# uARM.net
KiCad netlist of a schematic drawn in Altium Designer
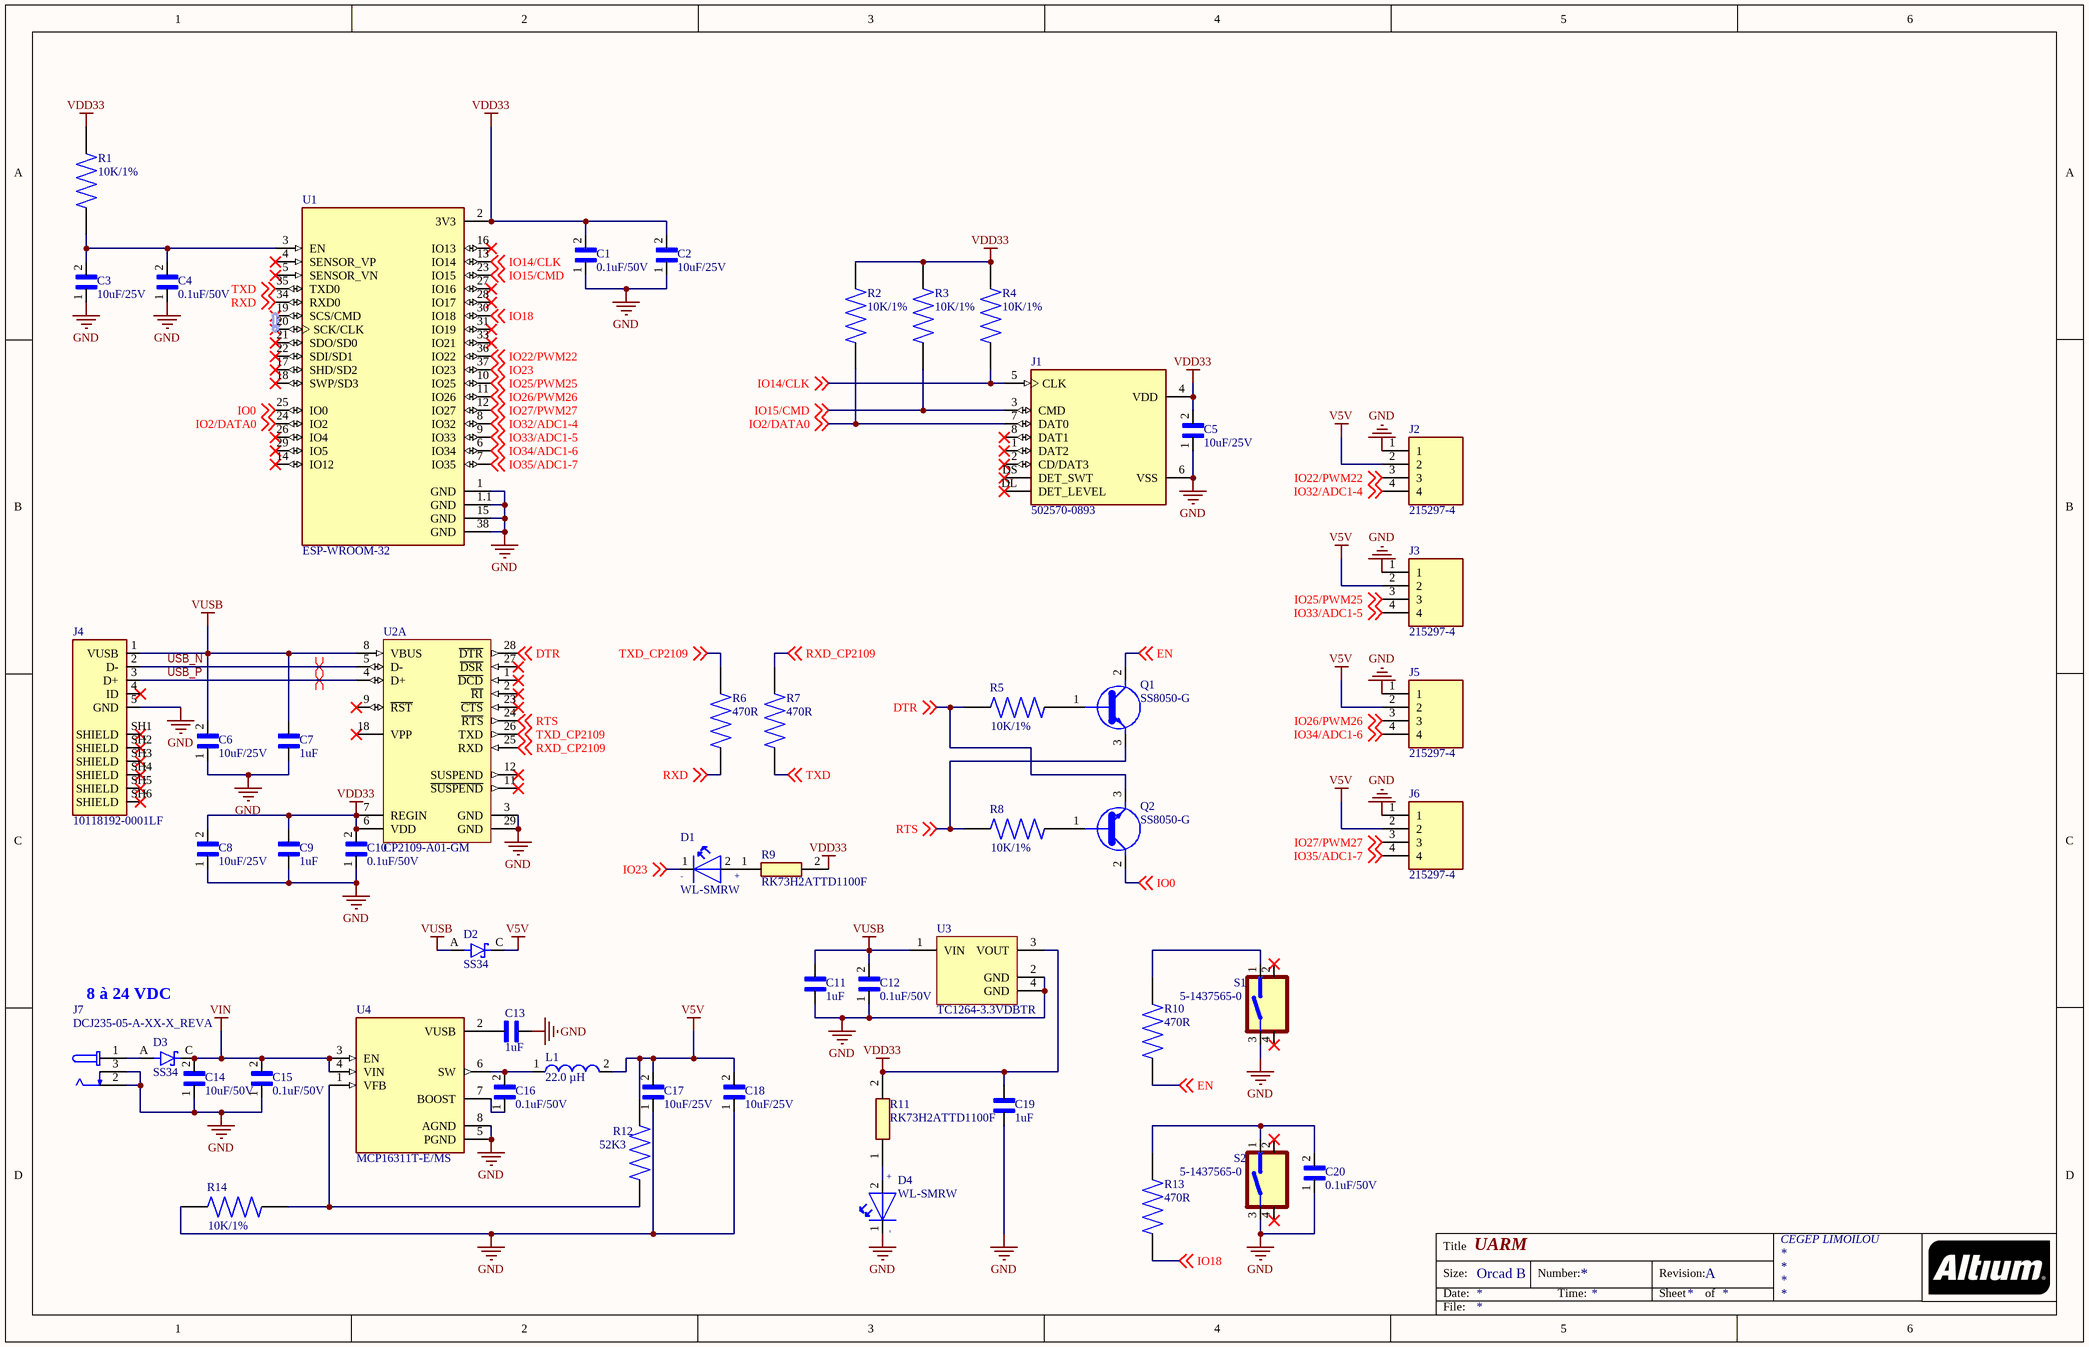
[diagram p0: uARM.SchDoc]

(export (version "E")
  (design (tool "Eeschema 10.0.6"))
  (components
    (comp (ref "C1")
      (value "0.1uF/50V")
      (footprint "RESC2012X60N")
      (description ".1UF 50V 10% 0805")
      (fields (field (name "MF") "{'manufacturer': u'AVX'}") (field (name "MP") "08055C104KAT4A"))
      (libsource (lib "*") (part "08055C104KAT4A"))
    )
    (comp (ref "C2")
      (value "10uF/25V")
      (footprint "RESC2012X60N")
      (description "Cap Ceramic 10uF 25V X5R 10% SMD 0805 85Â°C Embossed T/R")
      (fields (field (name "MP") "CL21A106KAYNNNE") (field (name "MF") "{'manufacturer': u'Samsung'}"))
      (libsource (lib "*") (part "CL21A106KAYNNNE"))
    )
    (comp (ref "C3")
      (value "10uF/25V")
      (footprint "RESC2012X60N")
      (description "Cap Ceramic 10uF 25V X5R 10% SMD 0805 85Â°C Embossed T/R")
      (fields (field (name "MP") "CL21A106KAYNNNE") (field (name "MF") "{'manufacturer': u'Samsung'}"))
      (libsource (lib "*") (part "CL21A106KAYNNNE"))
    )
    (comp (ref "C4")
      (value "0.1uF/50V")
      (footprint "RESC2012X60N")
      (description ".1UF 50V 10% 0805")
      (fields (field (name "MF") "{'manufacturer': u'AVX'}") (field (name "MP") "08055C104KAT4A"))
      (libsource (lib "*") (part "08055C104KAT4A"))
    )
    (comp (ref "C5")
      (value "10uF/25V")
      (footprint "CL21A106KAYNNNE:CAPC2012X135N")
      (description "Cap Ceramic 10uF 25V X5R 10% SMD 0805 85Â°C Embossed T/R")
      (fields (field (name "MP") "CL21A106KAYNNNE") (field (name "MF") "{'manufacturer': u'Samsung'}"))
      (libsource (lib "*") (part "CL21A106KAYNNNE"))
    )
    (comp (ref "C6")
      (value "10uF/25V")
      (footprint "CL21A106KAYNNNE:CAPC2012X135N")
      (description "Cap Ceramic 10uF 25V X5R 10% SMD 0805 85Â°C Embossed T/R")
      (fields (field (name "MP") "CL21A106KAYNNNE") (field (name "MF") "{'manufacturer': u'Samsung'}"))
      (libsource (lib "*") (part "CL21A106KAYNNNE"))
    )
    (comp (ref "C7")
      (value "1uF")
      (footprint "885012207022:WCAP-CSGP_885012207022")
      (fields
        (field (name "MF") "{'manufacturer': u'Wurth Electronics Inc'}")
        (field (name "MP") "885012207022")
      )
      (libsource (lib "*") (part "885012207022"))
    )
    (comp (ref "C8")
      (value "10uF/25V")
      (footprint "CL21A106KAYNNNE:CAPC2012X135N")
      (description "Cap Ceramic 10uF 25V X5R 10% SMD 0805 85Â°C Embossed T/R")
      (fields (field (name "MP") "CL21A106KAYNNNE") (field (name "MF") "{'manufacturer': u'Samsung'}"))
      (libsource (lib "*") (part "CL21A106KAYNNNE"))
    )
    (comp (ref "C9")
      (value "1uF")
      (footprint "885012207022:WCAP-CSGP_885012207022")
      (fields
        (field (name "MF") "{'manufacturer': u'Wurth Electronics Inc'}")
        (field (name "MP") "885012207022")
      )
      (libsource (lib "*") (part "885012207022"))
    )
    (comp (ref "C10")
      (value "0.1uF/50V")
      (footprint "08055C104KAT4A:CAPC2012X94N")
      (description ".1UF 50V 10% 0805")
      (fields (field (name "MF") "{'manufacturer': u'AVX'}") (field (name "MP") "08055C104KAT4A"))
      (libsource (lib "*") (part "08055C104KAT4A"))
    )
    (comp (ref "C11")
      (value "1uF")
      (footprint "885012207022:WCAP-CSGP_885012207022")
      (fields
        (field (name "MF") "{'manufacturer': u'Wurth Electronics Inc'}")
        (field (name "MP") "885012207022")
      )
      (libsource (lib "*") (part "885012207022"))
    )
    (comp (ref "C12")
      (value "0.1uF/50V")
      (footprint "08055C104KAT4A:CAPC2012X94N")
      (description ".1UF 50V 10% 0805")
      (fields (field (name "MF") "{'manufacturer': u'AVX'}") (field (name "MP") "08055C104KAT4A"))
      (libsource (lib "*") (part "08055C104KAT4A"))
    )
    (comp (ref "C13")
      (value "1uF")
      (footprint "885012207022:WCAP-CSGP_885012207022")
      (fields
        (field (name "MF") "{'manufacturer': u'Wurth Electronics Inc'}")
        (field (name "MP") "885012207022")
      )
      (libsource (lib "") (part "885012207022_1"))
    )
    (comp (ref "C14")
      (value "10uF/50V")
      (footprint "GRM21BR61H106KE43L:CAPC2012X145N")
      (description "SMD Capacitor X5R(EIA) with Capacitance: 10uF Tol. 10%. Rated Voltage: 50Vdc")
      (fields
        (field (name "MP") "GRM21BR61H106KE43L")
        (field (name "MF") "{'manufacturer': u'Murata Electronics'}")
      )
      (libsource (lib "*") (part "GRM21BR61H106KE43L"))
    )
    (comp (ref "C15")
      (value "0.1uF/50V")
      (footprint "08055C104KAT4A:CAPC2012X94N")
      (description ".1UF 50V 10% 0805")
      (fields (field (name "MF") "{'manufacturer': u'AVX'}") (field (name "MP") "08055C104KAT4A"))
      (libsource (lib "*") (part "08055C104KAT4A"))
    )
    (comp (ref "C16")
      (value "0.1uF/50V")
      (footprint "08055C104KAT4A:CAPC2012X94N")
      (description ".1UF 50V 10% 0805")
      (fields (field (name "MF") "{'manufacturer': u'AVX'}") (field (name "MP") "08055C104KAT4A"))
      (libsource (lib "*") (part "08055C104KAT4A"))
    )
    (comp (ref "C17")
      (value "10uF/25V")
      (footprint "CL21A106KAYNNNE:CAPC2012X135N")
      (description "Cap Ceramic 10uF 25V X5R 10% SMD 0805 85Â°C Embossed T/R")
      (fields (field (name "MP") "CL21A106KAYNNNE") (field (name "MF") "{'manufacturer': u'Samsung'}"))
      (libsource (lib "*") (part "CL21A106KAYNNNE"))
    )
    (comp (ref "C18")
      (value "10uF/25V")
      (footprint "CL21A106KAYNNNE:CAPC2012X135N")
      (description "Cap Ceramic 10uF 25V X5R 10% SMD 0805 85Â°C Embossed T/R")
      (fields (field (name "MP") "CL21A106KAYNNNE") (field (name "MF") "{'manufacturer': u'Samsung'}"))
      (libsource (lib "*") (part "CL21A106KAYNNNE"))
    )
    (comp (ref "C19")
      (value "1uF")
      (footprint "885012207022:WCAP-CSGP_885012207022")
      (fields
        (field (name "MF") "{'manufacturer': u'Wurth Electronics Inc'}")
        (field (name "MP") "885012207022")
      )
      (libsource (lib "*") (part "885012207022"))
    )
    (comp (ref "C20")
      (value "0.1uF/50V")
      (footprint "08055C104KAT4A:CAPC2012X94N")
      (description ".1UF 50V 10% 0805")
      (fields (field (name "MF") "{'manufacturer': u'AVX'}") (field (name "MP") "08055C104KAT4A"))
      (libsource (lib "*") (part "08055C104KAT4A"))
    )
    (comp (ref "D1")
      (value "WL-SMRW")
      (footprint "156120GS75000:WL-SMRW-1206-RECT")
      (fields (field (name "MF") "{'manufacturer': u'Wurth Electronics'}"))
      (libsource (lib "*") (part "WL-SMRW"))
    )
    (comp (ref "D2")
      (value "SS34")
      (footprint "SS34:DIOM7959X265N")
      (description "Diode Schottky 40V 3A 2-Pin SMC T/R")
      (fields (field (name "MF") "{'manufacturer': u'ON Semiconductor'}"))
      (libsource (lib "*") (part "SS34"))
    )
    (comp (ref "D3")
      (value "SS34")
      (footprint "SS34:DIOM7959X265N")
      (description "Diode Schottky 40V 3A 2-Pin SMC T/R")
      (fields (field (name "MF") "{'manufacturer': u'ON Semiconductor'}"))
      (libsource (lib "*") (part "SS34"))
    )
    (comp (ref "D4")
      (value "WL-SMRW")
      (footprint "156120GS75000:WL-SMRW-1206-RECT")
      (fields (field (name "MF") "{'manufacturer': u'Wurth Electronics'}"))
      (libsource (lib "*") (part "WL-SMRW"))
    )
    (comp (ref "J1")
      (value "502570-0893")
      (footprint "502570-0893:MOLEX_502570-0893")
      (fields (field (name "MF") "{'manufacturer': u'Molex'}"))
      (libsource (lib "*") (part "502570-0893"))
    )
    (comp (ref "J2")
      (value "215297-4")
      (footprint "215297-4:TE_215297-4")
      (fields (field (name "MF") "{'manufacturer': u'TE Connectivity'}"))
      (libsource (lib "*") (part "215297-4"))
    )
    (comp (ref "J3")
      (value "215297-4")
      (footprint "215297-4:TE_215297-4")
      (fields (field (name "MF") "{'manufacturer': u'TE Connectivity'}"))
      (libsource (lib "*") (part "215297-4"))
    )
    (comp (ref "J4")
      (value "10118192-0001LF")
      (footprint "10118192-0001LF:AMPHENOL_10118192-0001LF")
      (description "Single Port 5 Contact Horizontal Right Angle Shielded Micro B USB 2.0 Connector")
      (fields (field (name "MF") "{'manufacturer': u'FCI'}"))
      (libsource (lib "*") (part "10118192-0001LF"))
    )
    (comp (ref "J5")
      (value "215297-4")
      (footprint "215297-4:TE_215297-4")
      (fields (field (name "MF") "{'manufacturer': u'TE Connectivity'}"))
      (libsource (lib "*") (part "215297-4"))
    )
    (comp (ref "J6")
      (value "215297-4")
      (footprint "215297-4:TE_215297-4")
      (fields (field (name "MF") "{'manufacturer': u'TE Connectivity'}"))
      (libsource (lib "*") (part "215297-4"))
    )
    (comp (ref "J7")
      (value "DCJ235-05-A-XX-X_REVA")
      (footprint "DCJ235-05-A-K1-A:GCT_DCJ235-05-A-XX-X_REVA")
      (description "DC Power Jack, Thru-Hole, Horizontal, with Locating Pegs, D2.35mm")
      (fields (field (name "MF") "{'manufacturer': u'Global Connector Technology'}"))
      (libsource (lib "*") (part "DCJ235-05-A-XX-X_REVA"))
    )
    (comp (ref "L1")
      (value "744773122")
      (footprint "WE-PD2-S")
      (description "SMD Power Inductor WE-PD2, L = 22.0 µH")
      (fields (field (name "INDUCTANCE") "22.0 µH"))
      (libsource (lib "Wurth_Electronics_744773122") (part "744773122"))
    )
    (comp (ref "Q1")
      (value "SS8050-G")
      (footprint "SS8050-G:MBTB-T-SOT23")
      (fields (field (name "MF") "{'manufacturer': u'Comchip Technology'}"))
      (libsource (lib "*") (part "SS8050-G"))
    )
    (comp (ref "Q2")
      (value "SS8050-G")
      (footprint "SS8050-G:MBTB-T-SOT23")
      (fields (field (name "MF") "{'manufacturer': u'Comchip Technology'}"))
      (libsource (lib "*") (part "SS8050-G"))
    )
    (comp (ref "R1")
      (value "10K/1%")
      (footprint "ESR10EZPF1002:RESC2012X65N")
      (description "RES SMD 10K OHM 1% 0.4W 0805")
      (fields (field (name "MF") "{'manufacturer': u'Rohm'}") (field (name "MP") "ESR10EZPF1002"))
      (libsource (lib "*") (part "ESR10EZPF1002"))
    )
    (comp (ref "R2")
      (value "10K/1%")
      (footprint "ESR10EZPF1002:RESC2012X65N")
      (description "RES SMD 10K OHM 1% 0.4W 0805")
      (fields (field (name "MF") "{'manufacturer': u'Rohm'}") (field (name "MP") "ESR10EZPF1002"))
      (libsource (lib "*") (part "ESR10EZPF1002"))
    )
    (comp (ref "R3")
      (value "10K/1%")
      (footprint "ESR10EZPF1002:RESC2012X65N")
      (description "RES SMD 10K OHM 1% 0.4W 0805")
      (fields (field (name "MF") "{'manufacturer': u'Rohm'}") (field (name "MP") "ESR10EZPF1002"))
      (libsource (lib "*") (part "ESR10EZPF1002"))
    )
    (comp (ref "R4")
      (value "10K/1%")
      (footprint "ESR10EZPF1002:RESC2012X65N")
      (description "RES SMD 10K OHM 1% 0.4W 0805")
      (fields (field (name "MF") "{'manufacturer': u'Rohm'}") (field (name "MP") "ESR10EZPF1002"))
      (libsource (lib "*") (part "ESR10EZPF1002"))
    )
    (comp (ref "R5")
      (value "10K/1%")
      (footprint "ESR10EZPF1002:RESC2012X65N")
      (description "RES SMD 10K OHM 1% 0.4W 0805")
      (fields (field (name "MF") "{'manufacturer': u'Rohm'}") (field (name "MP") "ESR10EZPF1002"))
      (libsource (lib "*") (part "ESR10EZPF1002"))
    )
    (comp (ref "R6")
      (value "470R")
      (footprint "ERJ-PB6B4700V:RESC2012X70N")
      (fields (field (name "MP") "ERJ-PB6B4700V") (field (name "MF") "{'manufacturer': u'Panasonic'}"))
      (libsource (lib "*") (part "ERJ-PB6B4700V"))
    )
    (comp (ref "R7")
      (value "470R")
      (footprint "ERJ-PB6B4700V:RESC2012X70N")
      (fields (field (name "MP") "ERJ-PB6B4700V") (field (name "MF") "{'manufacturer': u'Panasonic'}"))
      (libsource (lib "*") (part "ERJ-PB6B4700V"))
    )
    (comp (ref "R8")
      (value "10K/1%")
      (footprint "ESR10EZPF1002:RESC2012X65N")
      (description "RES SMD 10K OHM 1% 0.4W 0805")
      (fields (field (name "MF") "{'manufacturer': u'Rohm'}") (field (name "MP") "ESR10EZPF1002"))
      (libsource (lib "*") (part "ESR10EZPF1002"))
    )
    (comp (ref "R9")
      (value "RK73H2ATTD1100F")
      (footprint "SamacSys:RESC2012X60N")
      (description "Resistor")
      (libsource (lib "*") (part "RK73H2ATTD1100F"))
    )
    (comp (ref "R10")
      (value "470R")
      (footprint "ERJ-PB6B4700V:RESC2012X70N")
      (fields (field (name "MP") "ERJ-PB6B4700V") (field (name "MF") "{'manufacturer': u'Panasonic'}"))
      (libsource (lib "*") (part "ERJ-PB6B4700V"))
    )
    (comp (ref "R11")
      (value "RK73H2ATTD1100F")
      (footprint "SamacSys:RESC2012X60N")
      (description "Resistor")
      (libsource (lib "") (part "RK73H2ATTD1100F_1"))
    )
    (comp (ref "R12")
      (value "52K3")
      (footprint "RESC2012X60N")
      (fields (field (name "MP") "ERJ-PB6B5232V"))
      (libsource (lib "ERJ-PB6B5232V") (part "ERJ-PB6B5232V"))
    )
    (comp (ref "R13")
      (value "470R")
      (footprint "ERJ-PB6B4700V:RESC2012X70N")
      (fields (field (name "MP") "ERJ-PB6B4700V") (field (name "MF") "{'manufacturer': u'Panasonic'}"))
      (libsource (lib "*") (part "ERJ-PB6B4700V"))
    )
    (comp (ref "R14")
      (value "10K/1%")
      (footprint "ESR10EZPF1002:RESC2012X65N")
      (description "RES SMD 10K OHM 1% 0.4W 0805")
      (fields (field (name "MF") "{'manufacturer': u'Rohm'}") (field (name "MP") "ESR10EZPF1002"))
      (libsource (lib "*") (part "ESR10EZPF1002"))
    )
    (comp (ref "S1")
      (value "5-1437565-0")
      (footprint "FSM6JSMATR:SW_5-1437565-0")
      (description "Switch Tactile OFF (ON) Round Button Gull Wing 0.05A 12VDC 1.57N SMD T/R")
      (fields (field (name "MF") "{'manufacturer': u'TE Connectivity'}"))
      (libsource (lib "*") (part "5-1437565-0"))
    )
    (comp (ref "S2")
      (value "5-1437565-0")
      (footprint "FSM6JSMATR:SW_5-1437565-0")
      (description "Switch Tactile OFF (ON) Round Button Gull Wing 0.05A 12VDC 1.57N SMD T/R")
      (fields (field (name "MF") "{'manufacturer': u'TE Connectivity'}"))
      (libsource (lib "*") (part "5-1437565-0"))
    )
    (comp (ref "U1")
      (value "ESP-WROOM-32")
      (footprint "ESP-WROOM-32:MODULE_ESP-WROOM-32")
      (description "Module: combo; GPIO, I2C x2, I2S x2, SDIO, SPI x3, UART x3; 19.5dBm")
      (fields (field (name "MF") "{'manufacturer': u'Espressif Systems'}"))
      (libsource (lib "*") (part "ESP-WROOM-32"))
    )
    (comp (ref "U2")
      (value "CP2109-A01-GM")
      (footprint "SLAB-QFN-28-3125x3125TP_L")
      (description "Single-Chip USB to UART Bridge, 1024 Bytes EEPROM, -40 to 85 degC, 28-pin QFN, Tube")
      (fields (field (name "MANUFACTURER") "Silicon Labs"))
      (libsource (lib "Silicon_Labs_CP2109_A01_GM") (part "CP2109-A01-GM"))
    )
    (comp (ref "U3")
      (value "TC1264-3.3VDBTR")
      (footprint "SOT-223-DB3_L")
      (description "800 mA Fixed-Output CMOS LDO with Shutdown, 3-Pin SOT-223, Extended Temperature, Tape and Reel")
      (libsource (lib "Microchip_TC1264_3_3VDBTR") (part "TC1264-3.3VDBTR"))
    )
    (comp (ref "U4")
      (value "MCP16311T-E/MS")
      (footprint "MCP16311T-E_MS:SOP65P490X110-8N")
      (fields (field (name "MF") "{'manufacturer': u'Microchip Technology'}"))
      (libsource (lib "*") (part "MCP16311T-E/MS"))
    )
  )
  (nets
    (net (code "1") (name "/USB_N") (class "Default")
      (node (ref "J4") (pin "2") (pinfunction "D-_2") (pintype "passive"))
      (node (ref "U2") (pin "5") (pinfunction "D-_5") (pintype "bidirectional"))
    )
    (net (code "2") (name "/USB_P") (class "Default")
      (node (ref "J4") (pin "3") (pinfunction "D+_3") (pintype "passive"))
      (node (ref "U2") (pin "4") (pinfunction "D+_4") (pintype "bidirectional"))
    )
    (net (code "3") (name "DTR") (class "Default")
      (node (ref "Q2") (pin "3") (pinfunction "C_3") (pintype "bidirectional"))
      (node (ref "R5") (pin "1") (pinfunction "1_1") (pintype "passive"))
      (node (ref "U2") (pin "28") (pinfunction "~{DTR}_28") (pintype "output"))
    )
    (net (code "4") (name "EN") (class "Default")
      (node (ref "Q1") (pin "2") (pinfunction "E_2") (pintype "bidirectional"))
      (node (ref "R10") (pin "1") (pinfunction "1_1") (pintype "passive"))
    )
    (net (code "5") (name "GND") (class "Default")
      (node (ref "C1") (pin "1") (pinfunction "1_1") (pintype "passive"))
      (node (ref "C10") (pin "1") (pinfunction "1_1") (pintype "passive"))
      (node (ref "C11") (pin "2") (pinfunction "2_2") (pintype "passive"))
      (node (ref "C12") (pin "1") (pinfunction "1_1") (pintype "passive"))
      (node (ref "C13") (pin "1") (pinfunction "1_1") (pintype "passive"))
      (node (ref "C14") (pin "1") (pinfunction "1_1") (pintype "passive"))
      (node (ref "C15") (pin "1") (pinfunction "1_1") (pintype "passive"))
      (node (ref "C17") (pin "1") (pinfunction "1_1") (pintype "passive"))
      (node (ref "C18") (pin "1") (pinfunction "1_1") (pintype "passive"))
      (node (ref "C19") (pin "2") (pinfunction "2_2") (pintype "passive"))
      (node (ref "C2") (pin "1") (pinfunction "1_1") (pintype "passive"))
      (node (ref "C20") (pin "1") (pinfunction "1_1") (pintype "passive"))
      (node (ref "C3") (pin "1") (pinfunction "1_1") (pintype "passive"))
      (node (ref "C4") (pin "1") (pinfunction "1_1") (pintype "passive"))
      (node (ref "C5") (pin "1") (pinfunction "1_1") (pintype "passive"))
      (node (ref "C6") (pin "1") (pinfunction "1_1") (pintype "passive"))
      (node (ref "C7") (pin "2") (pinfunction "2_2") (pintype "passive"))
      (node (ref "C8") (pin "1") (pinfunction "1_1") (pintype "passive"))
      (node (ref "C9") (pin "2") (pinfunction "2_2") (pintype "passive"))
      (node (ref "D4") (pin "1") (pinfunction "NEG_1") (pintype "bidirectional"))
      (node (ref "J1") (pin "6") (pinfunction "VSS_6") (pintype "power_in"))
      (node (ref "J2") (pin "1") (pinfunction "1_1") (pintype "passive"))
      (node (ref "J3") (pin "1") (pinfunction "1_1") (pintype "passive"))
      (node (ref "J4") (pin "5") (pinfunction "GND_5") (pintype "passive"))
      (node (ref "J5") (pin "1") (pinfunction "1_1") (pintype "passive"))
      (node (ref "J6") (pin "1") (pinfunction "1_1") (pintype "passive"))
      (node (ref "J7") (pin "2") (pinfunction "2_2") (pintype "passive"))
      (node (ref "J7") (pin "3") (pinfunction "3_3") (pintype "passive"))
      (node (ref "R14") (pin "1") (pinfunction "1_1") (pintype "passive"))
      (node (ref "S1") (pin "3") (pinfunction "1_3") (pintype "passive"))
      (node (ref "S2") (pin "3") (pinfunction "1_3") (pintype "passive"))
      (node (ref "U1") (pin "1") (pinfunction "GND_1") (pintype "power_in"))
      (node (ref "U1") (pin "1.1") (pinfunction "GND_1.1") (pintype "power_in"))
      (node (ref "U1") (pin "15") (pinfunction "GND_15") (pintype "power_in"))
      (node (ref "U1") (pin "38") (pinfunction "GND_38") (pintype "power_in"))
      (node (ref "U2") (pin "29") (pinfunction "GND_29") (pintype "power_in"))
      (node (ref "U2") (pin "3") (pinfunction "GND_3") (pintype "power_in"))
      (node (ref "U3") (pin "2") (pinfunction "GND_2") (pintype "power_in"))
      (node (ref "U3") (pin "4") (pinfunction "GND_4") (pintype "power_in"))
      (node (ref "U4") (pin "5") (pinfunction "PGND_5") (pintype "power_in"))
      (node (ref "U4") (pin "8") (pinfunction "AGND_8") (pintype "power_in"))
    )
    (net (code "6") (name "IO0") (class "Default")
      (node (ref "Q2") (pin "2") (pinfunction "E_2") (pintype "bidirectional"))
      (node (ref "U1") (pin "25") (pinfunction "IO0_25") (pintype "bidirectional"))
    )
    (net (code "7") (name "IO2{slash}DATA0") (class "Default")
      (node (ref "J1") (pin "7") (pinfunction "DAT0_7") (pintype "bidirectional"))
      (node (ref "R2") (pin "1") (pinfunction "1_1") (pintype "passive"))
      (node (ref "U1") (pin "24") (pinfunction "IO2_24") (pintype "bidirectional"))
    )
    (net (code "8") (name "IO14{slash}CLK") (class "Default")
      (node (ref "J1") (pin "5") (pinfunction "CLK_5") (pintype "input"))
      (node (ref "R4") (pin "1") (pinfunction "1_1") (pintype "passive"))
      (node (ref "U1") (pin "13") (pinfunction "IO14_13") (pintype "bidirectional"))
    )
    (net (code "9") (name "IO15{slash}CMD") (class "Default")
      (node (ref "J1") (pin "3") (pinfunction "CMD_3") (pintype "bidirectional"))
      (node (ref "R3") (pin "1") (pinfunction "1_1") (pintype "passive"))
      (node (ref "U1") (pin "23") (pinfunction "IO15_23") (pintype "bidirectional"))
    )
    (net (code "10") (name "IO18") (class "Default")
      (node (ref "R13") (pin "1") (pinfunction "1_1") (pintype "passive"))
      (node (ref "U1") (pin "30") (pinfunction "IO18_30") (pintype "bidirectional"))
    )
    (net (code "11") (name "IO22{slash}PWM22") (class "Default")
      (node (ref "J2") (pin "3") (pinfunction "3_3") (pintype "passive"))
      (node (ref "U1") (pin "36") (pinfunction "IO22_36") (pintype "bidirectional"))
    )
    (net (code "12") (name "IO23") (class "Default")
      (node (ref "D1") (pin "1") (pinfunction "NEG_1") (pintype "bidirectional"))
      (node (ref "U1") (pin "37") (pinfunction "IO23_37") (pintype "bidirectional"))
    )
    (net (code "13") (name "IO25{slash}PWM25") (class "Default")
      (node (ref "J3") (pin "3") (pinfunction "3_3") (pintype "passive"))
      (node (ref "U1") (pin "10") (pinfunction "IO25_10") (pintype "bidirectional"))
    )
    (net (code "14") (name "IO26{slash}PWM26") (class "Default")
      (node (ref "J5") (pin "3") (pinfunction "3_3") (pintype "passive"))
      (node (ref "U1") (pin "11") (pinfunction "IO26_11") (pintype "bidirectional"))
    )
    (net (code "15") (name "IO27{slash}PWM27") (class "Default")
      (node (ref "J6") (pin "3") (pinfunction "3_3") (pintype "passive"))
      (node (ref "U1") (pin "12") (pinfunction "IO27_12") (pintype "bidirectional"))
    )
    (net (code "16") (name "IO32{slash}ADC1-4") (class "Default")
      (node (ref "J2") (pin "4") (pinfunction "4_4") (pintype "passive"))
      (node (ref "U1") (pin "8") (pinfunction "IO32_8") (pintype "bidirectional"))
    )
    (net (code "17") (name "IO33{slash}ADC1-5") (class "Default")
      (node (ref "J3") (pin "4") (pinfunction "4_4") (pintype "passive"))
      (node (ref "U1") (pin "9") (pinfunction "IO33_9") (pintype "bidirectional"))
    )
    (net (code "18") (name "IO34{slash}ADC1-6") (class "Default")
      (node (ref "J5") (pin "4") (pinfunction "4_4") (pintype "passive"))
      (node (ref "U1") (pin "6") (pinfunction "IO34_6") (pintype "bidirectional"))
    )
    (net (code "19") (name "IO35{slash}ADC1-7") (class "Default")
      (node (ref "J6") (pin "4") (pinfunction "4_4") (pintype "passive"))
      (node (ref "U1") (pin "7") (pinfunction "IO35_7") (pintype "bidirectional"))
    )
    (net (code "20") (name "Net-(C20-Pad2)") (class "Default")
      (node (ref "C20") (pin "2") (pinfunction "2_2") (pintype "passive"))
      (node (ref "R13") (pin "2") (pinfunction "2_2") (pintype "passive"))
      (node (ref "S2") (pin "1") (pinfunction "2_1") (pintype "passive"))
    )
    (net (code "21") (name "Net-(D1-POS)") (class "Default")
      (node (ref "D1") (pin "2") (pinfunction "POS_2") (pintype "bidirectional"))
      (node (ref "R9") (pin "1") (pinfunction "1_1") (pintype "passive"))
    )
    (net (code "22") (name "Net-(D3-PadA)") (class "Default")
      (node (ref "D3") (pin "A") (pinfunction "A_A") (pintype "passive"))
      (node (ref "J7") (pin "1") (pinfunction "1_1") (pintype "passive"))
    )
    (net (code "23") (name "Net-(D4-POS)") (class "Default")
      (node (ref "D4") (pin "2") (pinfunction "POS_2") (pintype "bidirectional"))
      (node (ref "R11") (pin "1") (pinfunction "1_1") (pintype "passive"))
    )
    (net (code "24") (name "Net-(Q1-B)") (class "Default")
      (node (ref "Q1") (pin "1") (pinfunction "B_1") (pintype "bidirectional"))
      (node (ref "R5") (pin "2") (pinfunction "2_2") (pintype "passive"))
    )
    (net (code "25") (name "Net-(Q2-B)") (class "Default")
      (node (ref "Q2") (pin "1") (pinfunction "B_1") (pintype "bidirectional"))
      (node (ref "R8") (pin "2") (pinfunction "2_2") (pintype "passive"))
    )
    (net (code "26") (name "Net-(R10-Pad2)") (class "Default")
      (node (ref "R10") (pin "2") (pinfunction "2_2") (pintype "passive"))
      (node (ref "S1") (pin "1") (pinfunction "2_1") (pintype "passive"))
    )
    (net (code "27") (name "Net-(U1-EN)") (class "Default")
      (node (ref "C3") (pin "2") (pinfunction "2_2") (pintype "passive"))
      (node (ref "C4") (pin "2") (pinfunction "2_2") (pintype "passive"))
      (node (ref "R1") (pin "1") (pinfunction "1_1") (pintype "passive"))
      (node (ref "U1") (pin "3") (pinfunction "EN_3") (pintype "input"))
    )
    (net (code "28") (name "Net-(U4-BOOST)") (class "Default")
      (node (ref "C16") (pin "1") (pinfunction "1_1") (pintype "passive"))
      (node (ref "U4") (pin "7") (pinfunction "BOOST_7") (pintype "passive"))
    )
    (net (code "29") (name "Net-(U4-SW)") (class "Default")
      (node (ref "C16") (pin "2") (pinfunction "2_2") (pintype "passive"))
      (node (ref "L1") (pin "1") (pinfunction "1_1") (pintype "passive"))
      (node (ref "U4") (pin "6") (pinfunction "SW_6") (pintype "output"))
    )
    (net (code "30") (name "Net-(U4-VFB)") (class "Default")
      (node (ref "R12") (pin "1") (pinfunction "1_1") (pintype "passive"))
      (node (ref "R14") (pin "2") (pinfunction "2_2") (pintype "passive"))
      (node (ref "U4") (pin "1") (pinfunction "VFB_1") (pintype "input"))
    )
    (net (code "31") (name "Net-(U4-VUSB)") (class "Default")
      (node (ref "C13") (pin "2") (pinfunction "2_2") (pintype "passive"))
      (node (ref "U4") (pin "2") (pinfunction "VUSB_2") (pintype "power_in"))
    )
    (net (code "32") (name "RTS") (class "Default")
      (node (ref "Q1") (pin "3") (pinfunction "C_3") (pintype "bidirectional"))
      (node (ref "R8") (pin "1") (pinfunction "1_1") (pintype "passive"))
      (node (ref "U2") (pin "24") (pinfunction "~{RTS}_24") (pintype "output"))
    )
    (net (code "33") (name "RXD") (class "Default")
      (node (ref "R6") (pin "1") (pinfunction "1_1") (pintype "passive"))
      (node (ref "U1") (pin "34") (pinfunction "RXD0_34") (pintype "bidirectional"))
    )
    (net (code "34") (name "RXD_CP2109") (class "Default")
      (node (ref "R7") (pin "2") (pinfunction "2_2") (pintype "passive"))
      (node (ref "U2") (pin "25") (pinfunction "RXD_25") (pintype "input"))
    )
    (net (code "35") (name "TXD") (class "Default")
      (node (ref "R7") (pin "1") (pinfunction "1_1") (pintype "passive"))
      (node (ref "U1") (pin "35") (pinfunction "TXD0_35") (pintype "bidirectional"))
    )
    (net (code "36") (name "TXD_CP2109") (class "Default")
      (node (ref "R6") (pin "2") (pinfunction "2_2") (pintype "passive"))
      (node (ref "U2") (pin "26") (pinfunction "TXD_26") (pintype "output"))
    )
    (net (code "37") (name "V5V") (class "Default")
      (node (ref "C17") (pin "2") (pinfunction "2_2") (pintype "passive"))
      (node (ref "C18") (pin "2") (pinfunction "2_2") (pintype "passive"))
      (node (ref "D2") (pin "C") (pinfunction "K_C") (pintype "passive"))
      (node (ref "J2") (pin "2") (pinfunction "2_2") (pintype "passive"))
      (node (ref "J3") (pin "2") (pinfunction "2_2") (pintype "passive"))
      (node (ref "J5") (pin "2") (pinfunction "2_2") (pintype "passive"))
      (node (ref "J6") (pin "2") (pinfunction "2_2") (pintype "passive"))
      (node (ref "L1") (pin "2") (pinfunction "2_2") (pintype "passive"))
      (node (ref "R12") (pin "2") (pinfunction "2_2") (pintype "passive"))
    )
    (net (code "38") (name "VDD33") (class "Default")
      (node (ref "C1") (pin "2") (pinfunction "2_2") (pintype "passive"))
      (node (ref "C10") (pin "2") (pinfunction "2_2") (pintype "passive"))
      (node (ref "C19") (pin "1") (pinfunction "1_1") (pintype "passive"))
      (node (ref "C2") (pin "2") (pinfunction "2_2") (pintype "passive"))
      (node (ref "C5") (pin "2") (pinfunction "2_2") (pintype "passive"))
      (node (ref "C8") (pin "2") (pinfunction "2_2") (pintype "passive"))
      (node (ref "C9") (pin "1") (pinfunction "1_1") (pintype "passive"))
      (node (ref "J1") (pin "4") (pinfunction "VDD_4") (pintype "power_in"))
      (node (ref "R1") (pin "2") (pinfunction "2_2") (pintype "passive"))
      (node (ref "R11") (pin "2") (pinfunction "2_2") (pintype "passive"))
      (node (ref "R2") (pin "2") (pinfunction "2_2") (pintype "passive"))
      (node (ref "R3") (pin "2") (pinfunction "2_2") (pintype "passive"))
      (node (ref "R4") (pin "2") (pinfunction "2_2") (pintype "passive"))
      (node (ref "R9") (pin "2") (pinfunction "2_2") (pintype "passive"))
      (node (ref "U1") (pin "2") (pinfunction "3V3_2") (pintype "power_in"))
      (node (ref "U2") (pin "6") (pinfunction "VDD_6") (pintype "power_in"))
      (node (ref "U2") (pin "7") (pinfunction "REGIN_7") (pintype "power_in"))
      (node (ref "U3") (pin "3") (pinfunction "VOUT_3") (pintype "power_in"))
    )
    (net (code "39") (name "VIN") (class "Default")
      (node (ref "C14") (pin "2") (pinfunction "2_2") (pintype "passive"))
      (node (ref "C15") (pin "2") (pinfunction "2_2") (pintype "passive"))
      (node (ref "D3") (pin "C") (pinfunction "K_C") (pintype "passive"))
      (node (ref "U4") (pin "3") (pinfunction "EN_3") (pintype "input"))
      (node (ref "U4") (pin "4") (pinfunction "VIN_4") (pintype "input"))
    )
    (net (code "40") (name "VUSB") (class "Default")
      (node (ref "C11") (pin "1") (pinfunction "1_1") (pintype "passive"))
      (node (ref "C12") (pin "2") (pinfunction "2_2") (pintype "passive"))
      (node (ref "C6") (pin "2") (pinfunction "2_2") (pintype "passive"))
      (node (ref "C7") (pin "1") (pinfunction "1_1") (pintype "passive"))
      (node (ref "D2") (pin "A") (pinfunction "A_A") (pintype "passive"))
      (node (ref "J4") (pin "1") (pinfunction "VUSB_1") (pintype "passive"))
      (node (ref "U2") (pin "8") (pinfunction "VBUS_8") (pintype "input"))
      (node (ref "U3") (pin "1") (pinfunction "VIN_1") (pintype "power_in"))
    )
    (net (code "41") (name "unconnected-(J1-CD{slash}DAT3-Pad2)") (class "Default")
      (node (ref "J1") (pin "2") (pinfunction "CD/DAT3_2") (pintype "bidirectional+no_connect"))
    )
    (net (code "42") (name "unconnected-(J1-DAT1-Pad8)") (class "Default")
      (node (ref "J1") (pin "8") (pinfunction "DAT1_8") (pintype "bidirectional+no_connect"))
    )
    (net (code "43") (name "unconnected-(J1-DAT2-Pad1)") (class "Default")
      (node (ref "J1") (pin "1") (pinfunction "DAT2_1") (pintype "bidirectional+no_connect"))
    )
    (net (code "44") (name "unconnected-(J1-DET_LEVEL-PadDL)") (class "Default")
      (node (ref "J1") (pin "DL") (pinfunction "DET_LEVEL_DL") (pintype "passive+no_connect"))
    )
    (net (code "45") (name "unconnected-(J1-DET_SWT-PadDS)") (class "Default")
      (node (ref "J1") (pin "DS") (pinfunction "DET_SWT_DS") (pintype "passive+no_connect"))
    )
    (net (code "46") (name "unconnected-(J4-ID-Pad4)") (class "Default")
      (node (ref "J4") (pin "4") (pinfunction "ID_4") (pintype "passive+no_connect"))
    )
    (net (code "47") (name "unconnected-(J4-SHIELD-PadSH1)") (class "Default")
      (node (ref "J4") (pin "SH1") (pinfunction "SHIELD_SH1") (pintype "passive+no_connect"))
    )
    (net (code "48") (name "unconnected-(J4-SHIELD-PadSH2)") (class "Default")
      (node (ref "J4") (pin "SH2") (pinfunction "SHIELD_SH2") (pintype "passive+no_connect"))
    )
    (net (code "49") (name "unconnected-(J4-SHIELD-PadSH3)") (class "Default")
      (node (ref "J4") (pin "SH3") (pinfunction "SHIELD_SH3") (pintype "passive+no_connect"))
    )
    (net (code "50") (name "unconnected-(J4-SHIELD-PadSH4)") (class "Default")
      (node (ref "J4") (pin "SH4") (pinfunction "SHIELD_SH4") (pintype "passive+no_connect"))
    )
    (net (code "51") (name "unconnected-(J4-SHIELD-PadSH5)") (class "Default")
      (node (ref "J4") (pin "SH5") (pinfunction "SHIELD_SH5") (pintype "passive+no_connect"))
    )
    (net (code "52") (name "unconnected-(J4-SHIELD-PadSH6)") (class "Default")
      (node (ref "J4") (pin "SH6") (pinfunction "SHIELD_SH6") (pintype "passive+no_connect"))
    )
    (net (code "53") (name "unconnected-(S1-1-Pad4)") (class "Default")
      (node (ref "S1") (pin "4") (pinfunction "1_4") (pintype "passive+no_connect"))
    )
    (net (code "54") (name "unconnected-(S1-Pad2)") (class "Default")
      (node (ref "S1") (pin "2") (pinfunction "2_2") (pintype "passive+no_connect"))
    )
    (net (code "55") (name "unconnected-(S2-1-Pad4)") (class "Default")
      (node (ref "S2") (pin "4") (pinfunction "1_4") (pintype "passive+no_connect"))
    )
    (net (code "56") (name "unconnected-(S2-Pad2)") (class "Default")
      (node (ref "S2") (pin "2") (pinfunction "2_2") (pintype "passive+no_connect"))
    )
    (net (code "57") (name "unconnected-(U1-IO4-Pad26)") (class "Default")
      (node (ref "U1") (pin "26") (pinfunction "IO4_26") (pintype "bidirectional+no_connect"))
    )
    (net (code "58") (name "unconnected-(U1-IO5-Pad29)") (class "Default")
      (node (ref "U1") (pin "29") (pinfunction "IO5_29") (pintype "bidirectional+no_connect"))
    )
    (net (code "59") (name "unconnected-(U1-IO12-Pad14)") (class "Default")
      (node (ref "U1") (pin "14") (pinfunction "IO12_14") (pintype "bidirectional+no_connect"))
    )
    (net (code "60") (name "unconnected-(U1-IO13-Pad16)") (class "Default")
      (node (ref "U1") (pin "16") (pinfunction "IO13_16") (pintype "bidirectional+no_connect"))
    )
    (net (code "61") (name "unconnected-(U1-IO16-Pad27)") (class "Default")
      (node (ref "U1") (pin "27") (pinfunction "IO16_27") (pintype "bidirectional+no_connect"))
    )
    (net (code "62") (name "unconnected-(U1-IO17-Pad28)") (class "Default")
      (node (ref "U1") (pin "28") (pinfunction "IO17_28") (pintype "bidirectional+no_connect"))
    )
    (net (code "63") (name "unconnected-(U1-IO19-Pad31)") (class "Default")
      (node (ref "U1") (pin "31") (pinfunction "IO19_31") (pintype "bidirectional+no_connect"))
    )
    (net (code "64") (name "unconnected-(U1-IO21-Pad33)") (class "Default")
      (node (ref "U1") (pin "33") (pinfunction "IO21_33") (pintype "bidirectional+no_connect"))
    )
    (net (code "65") (name "unconnected-(U1-SCK{slash}CLK-Pad20)") (class "Default")
      (node (ref "U1") (pin "19") (pinfunction "SCS/CMD_19") (pintype "bidirectional"))
      (node (ref "U1") (pin "20") (pinfunction "SCK/CLK_20") (pintype "bidirectional"))
    )
    (net (code "66") (name "unconnected-(U1-SDI{slash}SD1-Pad22)") (class "Default")
      (node (ref "U1") (pin "22") (pinfunction "SDI/SD1_22") (pintype "bidirectional+no_connect"))
    )
    (net (code "67") (name "unconnected-(U1-SDO{slash}SD0-Pad21)") (class "Default")
      (node (ref "U1") (pin "21") (pinfunction "SDO/SD0_21") (pintype "bidirectional+no_connect"))
    )
    (net (code "68") (name "unconnected-(U1-SENSOR_VN-Pad5)") (class "Default")
      (node (ref "U1") (pin "5") (pinfunction "SENSOR_VN_5") (pintype "input+no_connect"))
    )
    (net (code "69") (name "unconnected-(U1-SENSOR_VP-Pad4)") (class "Default")
      (node (ref "U1") (pin "4") (pinfunction "SENSOR_VP_4") (pintype "input+no_connect"))
    )
    (net (code "70") (name "unconnected-(U1-SHD{slash}SD2-Pad17)") (class "Default")
      (node (ref "U1") (pin "17") (pinfunction "SHD/SD2_17") (pintype "bidirectional+no_connect"))
    )
    (net (code "71") (name "unconnected-(U1-SWP{slash}SD3-Pad18)") (class "Default")
      (node (ref "U1") (pin "18") (pinfunction "SWP/SD3_18") (pintype "bidirectional+no_connect"))
    )
    (net (code "72") (name "unconnected-(U2A-SUSPEND-Pad12)") (class "Default")
      (node (ref "U2") (pin "12") (pinfunction "SUSPEND_12") (pintype "output+no_connect"))
    )
    (net (code "73") (name "unconnected-(U2A-VPP-Pad18)") (class "Default")
      (node (ref "U2") (pin "18") (pinfunction "VPP_18") (pintype "passive+no_connect"))
    )
    (net (code "74") (name "unconnected-(U2A-~{CTS}-Pad23)") (class "Default")
      (node (ref "U2") (pin "23") (pinfunction "~{CTS}_23") (pintype "input+no_connect"))
    )
    (net (code "75") (name "unconnected-(U2A-~{DCD}-Pad1)") (class "Default")
      (node (ref "U2") (pin "1") (pinfunction "~{DCD}_1") (pintype "input+no_connect"))
    )
    (net (code "76") (name "unconnected-(U2A-~{DSR}-Pad27)") (class "Default")
      (node (ref "U2") (pin "27") (pinfunction "~{DSR}_27") (pintype "input+no_connect"))
    )
    (net (code "77") (name "unconnected-(U2A-~{RI}-Pad2)") (class "Default")
      (node (ref "U2") (pin "2") (pinfunction "~{RI}_2") (pintype "input+no_connect"))
    )
    (net (code "78") (name "unconnected-(U2A-~{RST}-Pad9)") (class "Default")
      (node (ref "U2") (pin "9") (pinfunction "~{RST}_9") (pintype "bidirectional+no_connect"))
    )
    (net (code "79") (name "unconnected-(U2A-~{SUSPEND}-Pad11)") (class "Default")
      (node (ref "U2") (pin "11") (pinfunction "~{SUSPEND}_11") (pintype "output+no_connect"))
    )
  )
)
